# 02_Top_Level.net
KiCad netlist of a schematic drawn in Altium Designer
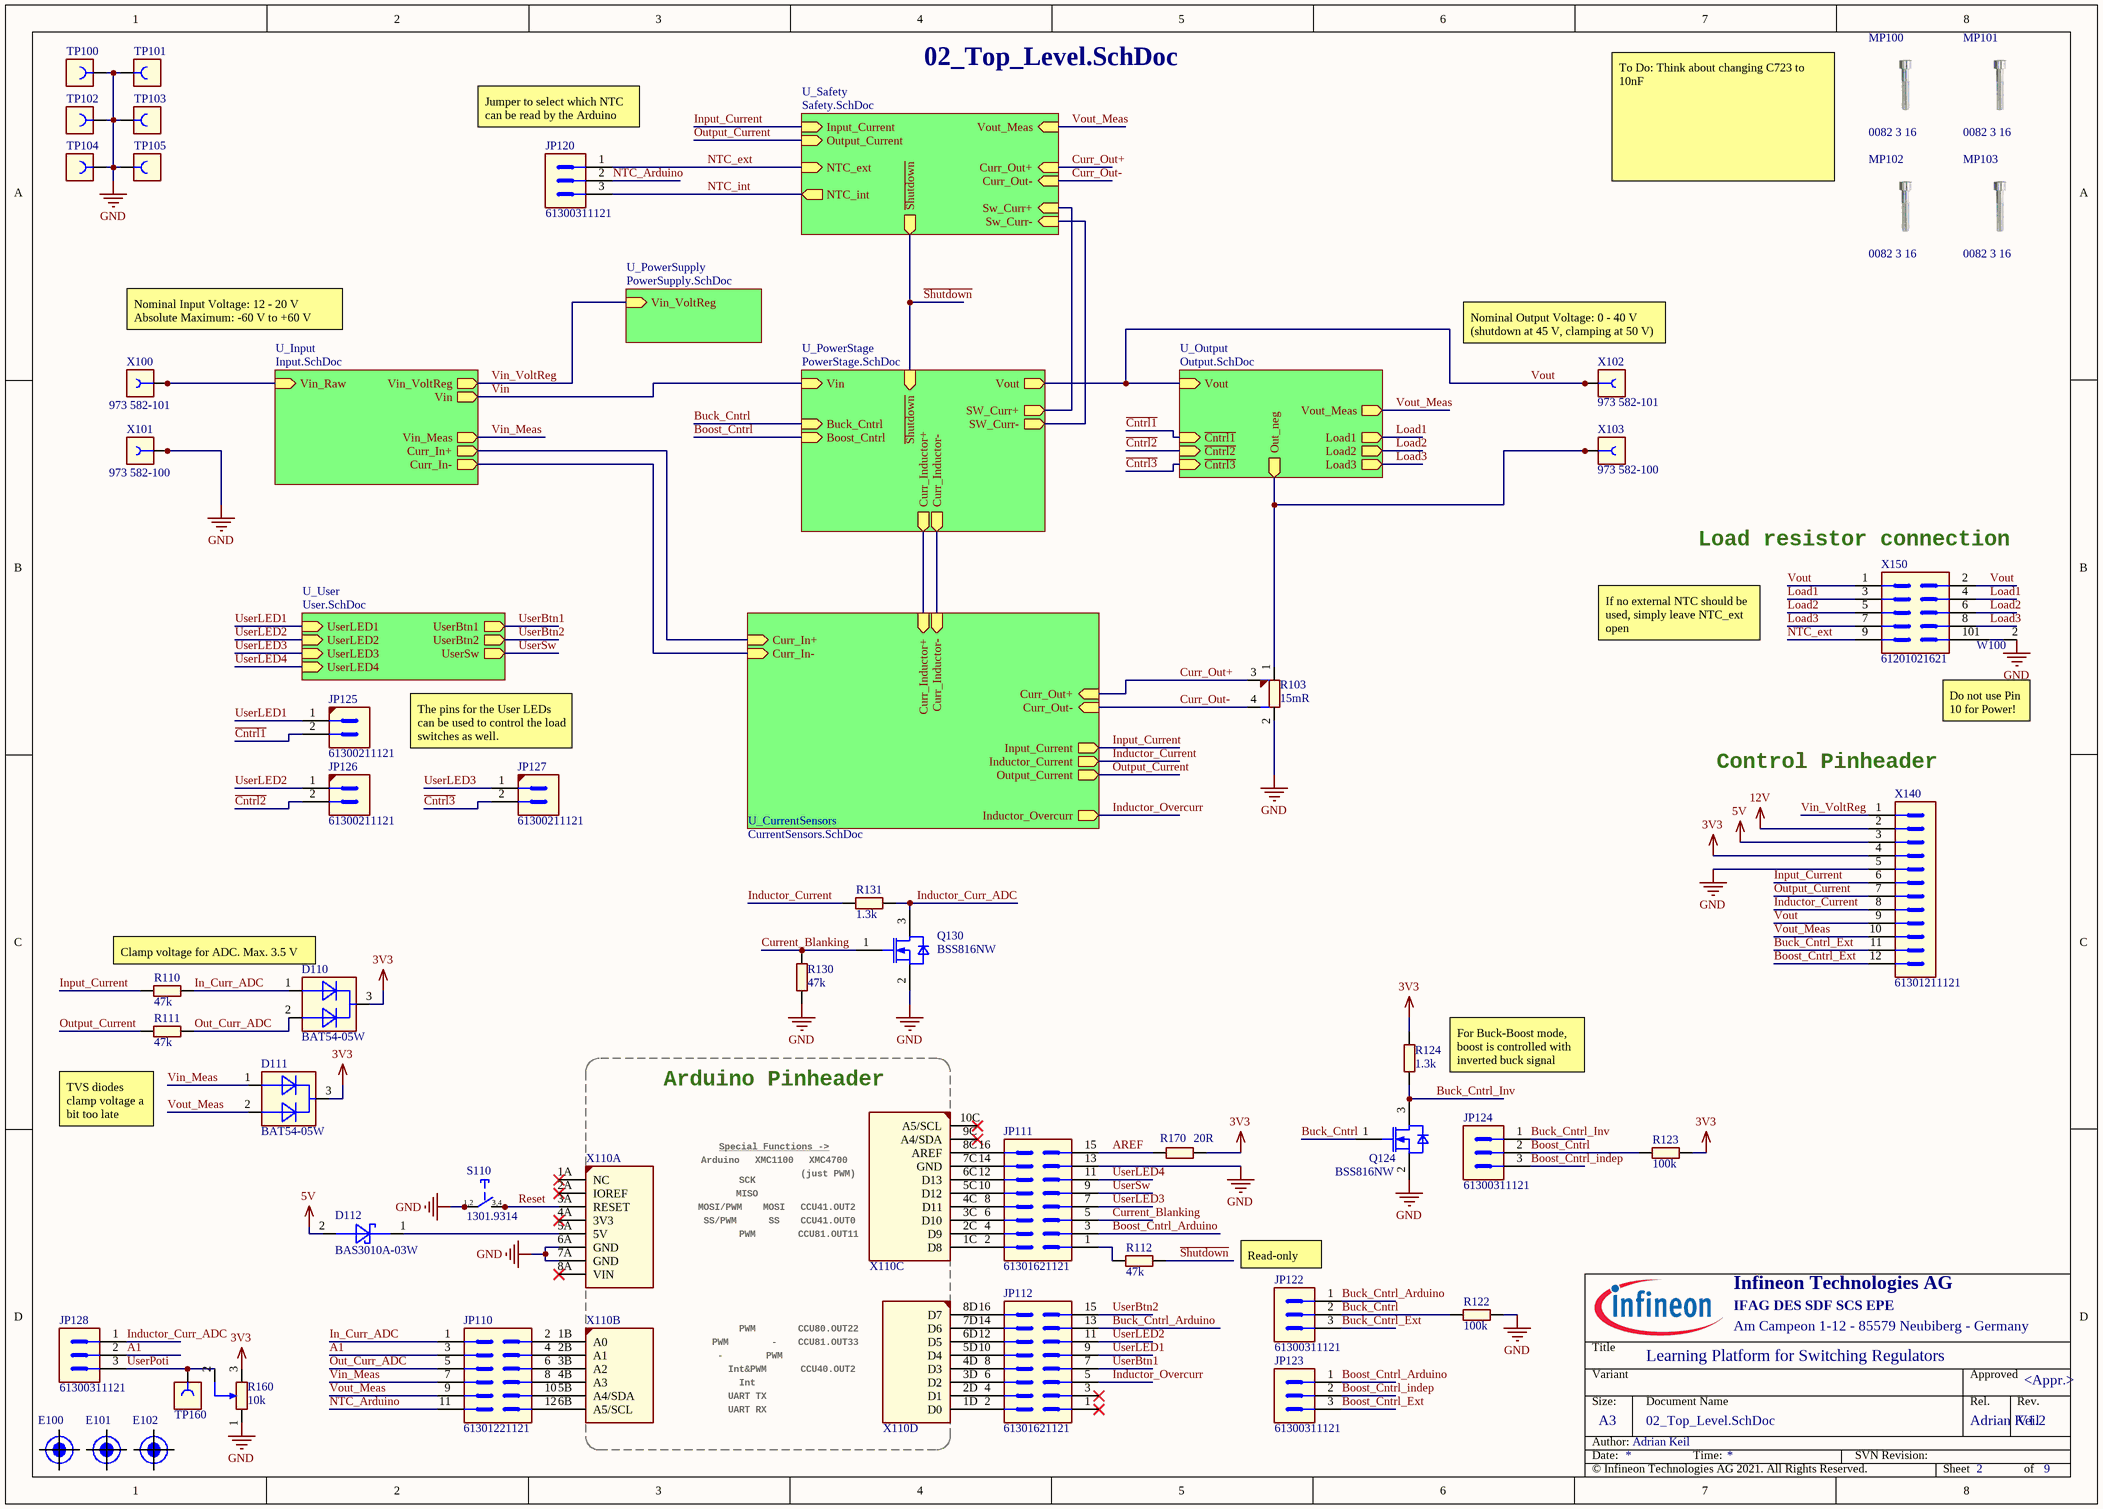
[diagram p0: 02_Top_Level.SchDoc]

(export (version "E")
  (design (tool "Eeschema 10.0.6"))
  (components
    (comp (ref "D110")
      (value "BAT54-05W")
      (footprint "SOT65P210X100-3N-1-V")
      (description "Silicon Schottky Diode, VR 30V")
      (fields (field (name "MANUFACTURER") "Infineon Technologies"))
      (libsource (lib "PCBLibraryData") (part "d_dual_a1a2c3_3p"))
    )
    (comp (ref "D111")
      (value "BAT54-05W")
      (footprint "SOT65P210X100-3N-1-V")
      (description "Silicon Schottky Diode, VR 30V")
      (fields (field (name "MANUFACTURER") "Infineon Technologies"))
      (libsource (lib "PCBLibraryData") (part "d_dual_a1a2c3_3p"))
    )
    (comp (ref "D112")
      (value "BAS3010A-03W")
      (footprint "SOD2513X110N")
      (description "Medium Power AF Schottky Diode")
      (fields
        (field (name "LEGACY PARTNUMBER") "IFX01400145")
        (field (name "MANUFACTURER") "Infineon Technologies")
      )
      (libsource (lib "PCBLibraryData") (part "d_schottky_a"))
    )
    (comp (ref "E100")
      (value "~")
      (footprint "fiducial")
      (description "Fiducial Mark")
      (fields
        (field (name "LEGACY PARTNUMBER") "MEC10000008")
        (field (name "MANUFACTURER") "Infineon Technologies")
      )
      (libsource (lib "PCBLibraryData") (part "fiducial"))
    )
    (comp (ref "E101")
      (value "~")
      (footprint "fiducial")
      (description "Fiducial Mark")
      (fields
        (field (name "LEGACY PARTNUMBER") "MEC10000008")
        (field (name "MANUFACTURER") "Infineon Technologies")
      )
      (libsource (lib "PCBLibraryData") (part "fiducial"))
    )
    (comp (ref "E102")
      (value "~")
      (footprint "fiducial")
      (description "Fiducial Mark")
      (fields
        (field (name "LEGACY PARTNUMBER") "MEC10000008")
        (field (name "MANUFACTURER") "Infineon Technologies")
      )
      (libsource (lib "PCBLibraryData") (part "fiducial"))
    )
    (comp (ref "JP110")
      (value "61301221121")
      (footprint "CON-M-THT-61301221121")
      (description "WR-PHD Dual Pin Header, 2.54mm Pitch, Double row, 12 Pins")
      (fields (field (name "MANUFACTURER") "Wurth Elektronik"))
      (libsource (lib "PCBLibraryData") (part "Header 6x2"))
    )
    (comp (ref "JP111")
      (value "61301621121")
      (footprint "CON-M-THT-61301621121")
      (description "Connector Header Through Hole 16 position 0.100 (2.54mm)")
      (fields (field (name "MANUFACTURER") "Wurth Elektronik"))
      (libsource (lib "PCBLibraryData") (part "Header 8X2"))
    )
    (comp (ref "JP112")
      (value "61301621121")
      (footprint "CON-M-THT-61301621121")
      (description "Connector Header Through Hole 16 position 0.100 (2.54mm)")
      (fields (field (name "MANUFACTURER") "Wurth Elektronik"))
      (libsource (lib "PCBLibraryData") (part "Header 8X2"))
    )
    (comp (ref "JP120")
      (value "61300311121")
      (footprint "CON-M-THT-61300311121")
      (description "WR-PHD Pin Header")
      (fields (field (name "MANUFACTURER") "Wurth Elektronik"))
      (libsource (lib "PCBLibraryData") (part "Header 3"))
    )
    (comp (ref "JP122")
      (value "61300311121")
      (footprint "CON-M-THT-61300311121")
      (description "WR-PHD Pin Header")
      (fields (field (name "MANUFACTURER") "Wurth Elektronik"))
      (libsource (lib "PCBLibraryData") (part "Header 3"))
    )
    (comp (ref "JP123")
      (value "61300311121")
      (footprint "CON-M-THT-61300311121")
      (description "WR-PHD Pin Header")
      (fields (field (name "MANUFACTURER") "Wurth Elektronik"))
      (libsource (lib "PCBLibraryData") (part "Header 3"))
    )
    (comp (ref "JP124")
      (value "61300311121")
      (footprint "CON-M-THT-61300311121")
      (description "WR-PHD Pin Header")
      (fields (field (name "MANUFACTURER") "Wurth Elektronik"))
      (libsource (lib "PCBLibraryData") (part "Header 3"))
    )
    (comp (ref "JP125")
      (value "61300211121")
      (footprint "CON-M-THT-61300211121")
      (description "Header, 2.54mm Pitch, 2 pin, Vertical, Single Row")
      (fields
        (field (name "LEGACY PARTNUMBER") "CON01500943")
        (field (name "MANUFACTURER") "Wurth Elektronik")
      )
      (libsource (lib "PCBLibraryData") (part "Header 2"))
    )
    (comp (ref "JP126")
      (value "61300211121")
      (footprint "CON-M-THT-61300211121")
      (description "Header, 2.54mm Pitch, 2 pin, Vertical, Single Row")
      (fields
        (field (name "LEGACY PARTNUMBER") "CON01500943")
        (field (name "MANUFACTURER") "Wurth Elektronik")
      )
      (libsource (lib "PCBLibraryData") (part "Header 2"))
    )
    (comp (ref "JP127")
      (value "61300211121")
      (footprint "CON-M-THT-61300211121")
      (description "Header, 2.54mm Pitch, 2 pin, Vertical, Single Row")
      (fields
        (field (name "LEGACY PARTNUMBER") "CON01500943")
        (field (name "MANUFACTURER") "Wurth Elektronik")
      )
      (libsource (lib "PCBLibraryData") (part "Header 2"))
    )
    (comp (ref "JP128")
      (value "61300311121")
      (footprint "CON-M-THT-61300311121")
      (description "WR-PHD Pin Header")
      (fields (field (name "MANUFACTURER") "Wurth Elektronik"))
      (libsource (lib "PCBLibraryData") (part "Header 3"))
    )
    (comp (ref "MP100")
      (value "0082 3 16")
      (footprint "SCREW_0082 3 16_NPTH")
      (description "Cheese Head Screw With Hexagon Socket, DIN 912 (ISO 4762), M3, 16mm length")
      (fields
        (field (name "LEGACY PARTNUMBER") "MEC10000167")
        (field (name "MANUFACTURER") "Wurth Elektronik")
      )
      (libsource (lib "PCBLibraryData") (part "Screw_0082 3 16"))
    )
    (comp (ref "MP101")
      (value "0082 3 16")
      (footprint "SCREW_0082 3 16_NPTH")
      (description "Cheese Head Screw With Hexagon Socket, DIN 912 (ISO 4762), M3, 16mm length")
      (fields
        (field (name "LEGACY PARTNUMBER") "MEC10000167")
        (field (name "MANUFACTURER") "Wurth Elektronik")
      )
      (libsource (lib "PCBLibraryData") (part "Screw_0082 3 16"))
    )
    (comp (ref "MP102")
      (value "0082 3 16")
      (footprint "SCREW_0082 3 16_NPTH")
      (description "Cheese Head Screw With Hexagon Socket, DIN 912 (ISO 4762), M3, 16mm length")
      (fields
        (field (name "LEGACY PARTNUMBER") "MEC10000167")
        (field (name "MANUFACTURER") "Wurth Elektronik")
      )
      (libsource (lib "PCBLibraryData") (part "Screw_0082 3 16"))
    )
    (comp (ref "MP103")
      (value "0082 3 16")
      (footprint "SCREW_0082 3 16_NPTH")
      (description "Cheese Head Screw With Hexagon Socket, DIN 912 (ISO 4762), M3, 16mm length")
      (fields
        (field (name "LEGACY PARTNUMBER") "MEC10000167")
        (field (name "MANUFACTURER") "Wurth Elektronik")
      )
      (libsource (lib "PCBLibraryData") (part "Screw_0082 3 16"))
    )
    (comp (ref "Q124")
      (value "BSS816NW")
      (footprint "SOT65P210X100-3N-1-V")
      (description "OptiMOS 2 Small-Signal-Transistor")
      (fields (field (name "MANUFACTURER") "Infineon Technologies"))
      (libsource (lib "PCBLibraryData") (part "igfet_n_ch_dep_dio_1g2s3d_3p"))
    )
    (comp (ref "Q130")
      (value "BSS816NW")
      (footprint "SOT65P210X100-3N-1-V")
      (description "OptiMOS 2 Small-Signal-Transistor")
      (fields (field (name "MANUFACTURER") "Infineon Technologies"))
      (libsource (lib "PCBLibraryData") (part "igfet_n_ch_dep_dio_1g2s3d_3p"))
    )
    (comp (ref "R103")
      (value "15mR")
      (footprint "RES-SMD-L4T12")
      (description "RES / STD / 15mR / 500mW / 1% / 75ppm/K / -55°C to 155°C / 1206 (3216) / SMD / -")
      (fields (field (name "MANUFACTURER") "Ohmite"))
      (libsource (lib "PCBLibraryData") (part "RES-SHT-STD-04P_00097BE5"))
    )
    (comp (ref "R110")
      (value "47k")
      (footprint "RESC1609X50N")
      (description "RES / STD / 47k / 100mW / 1% / 100ppm/K / -55°C to 155°C / 0603 / SMD / -")
      (fields (field (name "LEGACY PARTNUMBER") "RES01801333") (field (name "MANUFACTURER") "Vishay"))
      (libsource (lib "PCBLibraryData") (part "RES-SGL-STD-02P_00000006"))
    )
    (comp (ref "R111")
      (value "47k")
      (footprint "RESC1609X50N")
      (description "RES / STD / 47k / 100mW / 1% / 100ppm/K / -55°C to 155°C / 0603 / SMD / -")
      (fields (field (name "LEGACY PARTNUMBER") "RES01801333") (field (name "MANUFACTURER") "Vishay"))
      (libsource (lib "PCBLibraryData") (part "RES-SGL-STD-02P_00000006"))
    )
    (comp (ref "R112")
      (value "47k")
      (footprint "RESC1609X50N")
      (description "RES / STD / 47k / 100mW / 1% / 100ppm/K / -55°C to 155°C / 0603 / SMD / -")
      (fields (field (name "LEGACY PARTNUMBER") "RES01801333") (field (name "MANUFACTURER") "Vishay"))
      (libsource (lib "PCBLibraryData") (part "RES-SGL-STD-02P_00000006"))
    )
    (comp (ref "R122")
      (value "100k")
      (footprint "RESC1609X50N")
      (description "RES / STD / 100k / 100mW / 1% / 100ppm/K / -55°C to 155°C / 0603 / SMD / -")
      (fields (field (name "LEGACY PARTNUMBER") "RES01801371") (field (name "MANUFACTURER") "Vishay"))
      (libsource (lib "PCBLibraryData") (part "RES-SGL-STD-02P_00000006"))
    )
    (comp (ref "R123")
      (value "100k")
      (footprint "RESC1609X50N")
      (description "RES / STD / 100k / 100mW / 1% / 100ppm/K / -55°C to 155°C / 0603 / SMD / -")
      (fields (field (name "LEGACY PARTNUMBER") "RES01801371") (field (name "MANUFACTURER") "Vishay"))
      (libsource (lib "PCBLibraryData") (part "RES-SGL-STD-02P_00000006"))
    )
    (comp (ref "R124")
      (value "1.3k")
      (footprint "RESC1609X50N")
      (description "RES / STD / 1.3k / 100mW / 1% / 100ppm/K / -55°C to 155°C / 0603 / SMD / -")
      (fields (field (name "LEGACY PARTNUMBER") "RES01801155") (field (name "MANUFACTURER") "Vishay"))
      (libsource (lib "") (part "RES-SGL-STD-02P_00000006_1"))
    )
    (comp (ref "R130")
      (value "47k")
      (footprint "RESC1609X50N")
      (description "RES / STD / 47k / 100mW / 1% / 100ppm/K / -55°C to 155°C / 0603 / SMD / -")
      (fields (field (name "LEGACY PARTNUMBER") "RES01801333") (field (name "MANUFACTURER") "Vishay"))
      (libsource (lib "") (part "RES-SGL-STD-02P_00000006_1"))
    )
    (comp (ref "R131")
      (value "1.3k")
      (footprint "RESC1609X50N")
      (description "RES / STD / 1.3k / 100mW / 1% / 100ppm/K / -55°C to 155°C / 0603 / SMD / -")
      (fields (field (name "LEGACY PARTNUMBER") "RES01801155") (field (name "MANUFACTURER") "Vishay"))
      (libsource (lib "PCBLibraryData") (part "RES-SGL-STD-02P_00000006"))
    )
    (comp (ref "R160")
      (value "10k")
      (footprint "POT-SMD-3361P")
      (fields (field (name "MANUFACTURER") "Bourns"))
      (libsource (lib "PCBLibraryData") (part "RES-SGL-VAR-03P_00000026"))
    )
    (comp (ref "R170")
      (value "20R")
      (footprint "RESC1609X50N")
      (description "RES / STD / 20R / 100mW / 1% / 100ppm/K / -55°C to 155°C / 0603 / SMD / -")
      (fields (field (name "LEGACY PARTNUMBER") "RES01800947") (field (name "MANUFACTURER") "Vishay"))
      (libsource (lib "") (part "RES-SGL-STD-02P_00000006_2"))
    )
    (comp (ref "S110")
      (value "1301.9314")
      (footprint "SW-SMD-1301.9314")
      (description "Pushbutton Tactile Switch, Single Pole Single Throw, 4 Pins")
      (fields (field (name "LEGACY PARTNUMBER") "CON01500305") (field (name "MANUFACTURER") "Schurter"))
      (libsource (lib "PCBLibraryData") (part "sw_sr_no12_34_4p"))
    )
    (comp (ref "TP100")
      (value "5011")
      (footprint "CON-THT-TP-5011")
      (description "PC Test Point-Multipurpose THT, Black")
      (fields
        (field (name "LEGACY PARTNUMBER") "CON01500530")
        (field (name "MANUFACTURER") "Keystone Electronics Corp.")
      )
      (libsource (lib "PCBLibraryData") (part "connector_1_f"))
    )
    (comp (ref "TP101")
      (value "5011")
      (footprint "CON-THT-TP-5011")
      (description "PC Test Point-Multipurpose THT, Black")
      (fields
        (field (name "LEGACY PARTNUMBER") "CON01500530")
        (field (name "MANUFACTURER") "Keystone Electronics Corp.")
      )
      (libsource (lib "") (part "connector_1_f_1"))
    )
    (comp (ref "TP102")
      (value "5011")
      (footprint "CON-THT-TP-5011")
      (description "PC Test Point-Multipurpose THT, Black")
      (fields
        (field (name "LEGACY PARTNUMBER") "CON01500530")
        (field (name "MANUFACTURER") "Keystone Electronics Corp.")
      )
      (libsource (lib "PCBLibraryData") (part "connector_1_f"))
    )
    (comp (ref "TP103")
      (value "5011")
      (footprint "CON-THT-TP-5011")
      (description "PC Test Point-Multipurpose THT, Black")
      (fields
        (field (name "LEGACY PARTNUMBER") "CON01500530")
        (field (name "MANUFACTURER") "Keystone Electronics Corp.")
      )
      (libsource (lib "") (part "connector_1_f_1"))
    )
    (comp (ref "TP104")
      (value "5011")
      (footprint "CON-THT-TP-5011")
      (description "PC Test Point-Multipurpose THT, Black")
      (fields
        (field (name "LEGACY PARTNUMBER") "CON01500530")
        (field (name "MANUFACTURER") "Keystone Electronics Corp.")
      )
      (libsource (lib "PCBLibraryData") (part "connector_1_f"))
    )
    (comp (ref "TP105")
      (value "5011")
      (footprint "CON-THT-TP-5011")
      (description "PC Test Point-Multipurpose THT, Black")
      (fields
        (field (name "LEGACY PARTNUMBER") "CON01500530")
        (field (name "MANUFACTURER") "Keystone Electronics Corp.")
      )
      (libsource (lib "") (part "connector_1_f_1"))
    )
    (comp (ref "TP160")
      (value "S1751-46R")
      (footprint "CON-SMD-TT-S1751-46")
      (description "Test Terminal, Surface Mount (Tape and Reeled Components)")
      (fields (field (name "LEGACY PARTNUMBER") "CON01501015") (field (name "MANUFACTURER") "Harwin"))
      (libsource (lib "") (part "connector_1_f_2"))
    )
    (comp (ref "W100")
      (value "Net_Tie_2")
      (footprint "Net_Tie_Small_2P")
      (description "SMD Net Tie for two Nets")
      (fields
        (field (name "LEGACY PARTNUMBER") "CON01501379")
        (field (name "MANUFACTURER") "Infineon Technologies")
      )
      (libsource (lib "PCBLibraryData") (part "Net_Tie_2"))
    )
    (comp (ref "X100")
      (value "973 582-101")
      (footprint "CON-THT-973 582- 101")
      (description "Banana Socket, Red, 17.5mm Pitch")
      (fields
        (field (name "LEGACY PARTNUMBER") "CON01500041")
        (field (name "MANUFACTURER") "Hirschmann Test & Measurement")
      )
      (libsource (lib "PCBLibraryData") (part "soc_banana_2p"))
    )
    (comp (ref "X101")
      (value "973 582-100")
      (footprint "CON-THT-973 582- 100")
      (description "Banana Socket, black, 17.5mm Pitch")
      (fields
        (field (name "LEGACY PARTNUMBER") "CON01500045")
        (field (name "MANUFACTURER") "Hirschmann Test & Measurement")
      )
      (libsource (lib "PCBLibraryData") (part "soc_banana_2p"))
    )
    (comp (ref "X102")
      (value "973 582-101")
      (footprint "CON-THT-973 582- 101")
      (description "Banana Socket, Red, 17.5mm Pitch")
      (fields
        (field (name "LEGACY PARTNUMBER") "CON01500041")
        (field (name "MANUFACTURER") "Hirschmann Test & Measurement")
      )
      (libsource (lib "") (part "soc_banana_2p_1"))
    )
    (comp (ref "X103")
      (value "973 582-100")
      (footprint "CON-THT-973 582- 100")
      (description "Banana Socket, black, 17.5mm Pitch")
      (fields
        (field (name "LEGACY PARTNUMBER") "CON01500045")
        (field (name "MANUFACTURER") "Hirschmann Test & Measurement")
      )
      (libsource (lib "") (part "soc_banana_2p_1"))
    )
    (comp (ref "X110")
      (value "Arduino-Uno")
      (footprint "Arduino-Uno")
      (description "Arduino Uno is a microcontroller board based on the ATmega328P")
      (fields (field (name "MANUFACTURER") "Infineon Technologies"))
      (libsource (lib "") (part "Arduino-Uno_1"))
    )
    (comp (ref "X140")
      (value "61301211121")
      (footprint "CON-M-THT-61301211121")
      (description "WR-PHD Pin Header")
      (fields (field (name "MANUFACTURER") "Wurth Elektronik"))
      (libsource (lib "PCBLibraryData") (part "Header 12"))
    )
    (comp (ref "X150")
      (value "61201021621")
      (footprint "CON-M-THT-61201021621")
      (description "WR-BHD Male Box Header, 2.54mm pitch, 10 pin, Vertical, Double row")
      (fields (field (name "MANUFACTURER") "Wurth Elektronik"))
      (libsource (lib "PCBLibraryData") (part "Header 5X2"))
    )
  )
  (nets
    (net (code "1") (name "/A1") (class "Default")
      (node (ref "JP110") (pin "3") (pinfunction "3_3") (pintype "passive"))
      (node (ref "JP128") (pin "2") (pinfunction "2_2") (pintype "passive"))
    )
    (net (code "2") (name "/AREF") (class "Default")
      (node (ref "JP111") (pin "15") (pinfunction "15_15") (pintype "passive"))
      (node (ref "R170") (pin "1") (pinfunction "1_1") (pintype "passive"))
    )
    (net (code "3") (name "/Boost_Cntrl") (class "Default")
      (node (ref "JP124") (pin "2") (pinfunction "2_2") (pintype "passive"))
      (node (ref "R123") (pin "2") (pinfunction "2_2") (pintype "passive"))
    )
    (net (code "4") (name "/Boost_Cntrl_Arduino") (class "Default")
      (node (ref "JP111") (pin "3") (pinfunction "3_3") (pintype "passive"))
      (node (ref "JP123") (pin "1") (pinfunction "1_1") (pintype "passive"))
    )
    (net (code "5") (name "/Boost_Cntrl_Ext") (class "Default")
      (node (ref "JP123") (pin "3") (pinfunction "3_3") (pintype "passive"))
      (node (ref "X140") (pin "12") (pinfunction "12_12") (pintype "passive"))
    )
    (net (code "6") (name "/Boost_Cntrl_indep") (class "Default")
      (node (ref "JP123") (pin "2") (pinfunction "2_2") (pintype "passive"))
      (node (ref "JP124") (pin "3") (pinfunction "3_3") (pintype "passive"))
    )
    (net (code "7") (name "/Buck_Cntrl") (class "Default")
      (node (ref "JP122") (pin "2") (pinfunction "2_2") (pintype "passive"))
      (node (ref "Q124") (pin "1") (pinfunction "GATE_1") (pintype "passive"))
      (node (ref "R122") (pin "2") (pinfunction "2_2") (pintype "passive"))
    )
    (net (code "8") (name "/Buck_Cntrl_Arduino") (class "Default")
      (node (ref "JP112") (pin "13") (pinfunction "13_13") (pintype "passive"))
      (node (ref "JP122") (pin "1") (pinfunction "1_1") (pintype "passive"))
    )
    (net (code "9") (name "/Buck_Cntrl_Ext") (class "Default")
      (node (ref "JP122") (pin "3") (pinfunction "3_3") (pintype "passive"))
      (node (ref "X140") (pin "11") (pinfunction "11_11") (pintype "passive"))
    )
    (net (code "10") (name "/Buck_Cntrl_Inv") (class "Default")
      (node (ref "JP124") (pin "1") (pinfunction "1_1") (pintype "passive"))
      (node (ref "Q124") (pin "3") (pinfunction "DRAIN_3") (pintype "passive"))
      (node (ref "R124") (pin "1") (pinfunction "1_1") (pintype "passive"))
    )
    (net (code "11") (name "/Cntrl1") (class "Default")
      (node (ref "JP125") (pin "2") (pinfunction "2_2") (pintype "passive"))
    )
    (net (code "12") (name "/Cntrl2") (class "Default")
      (node (ref "JP126") (pin "2") (pinfunction "2_2") (pintype "passive"))
    )
    (net (code "13") (name "/Cntrl3") (class "Default")
      (node (ref "JP127") (pin "2") (pinfunction "2_2") (pintype "passive"))
    )
    (net (code "18") (name "/Curr_Out+") (class "Default")
      (node (ref "R103") (pin "3") (pinfunction "I1_3") (pintype "passive"))
    )
    (net (code "19") (name "/Curr_Out-") (class "Default")
      (node (ref "R103") (pin "4") (pinfunction "I2_4") (pintype "passive"))
    )
    (net (code "20") (name "/Current_Blanking") (class "Default")
      (node (ref "JP111") (pin "5") (pinfunction "5_5") (pintype "passive"))
      (node (ref "Q130") (pin "1") (pinfunction "GATE_1") (pintype "passive"))
      (node (ref "R130") (pin "2") (pinfunction "2_2") (pintype "passive"))
    )
    (net (code "21") (name "/In_Curr_ADC") (class "Default")
      (node (ref "D110") (pin "1") (pinfunction "ANODE_1_1") (pintype "passive"))
      (node (ref "JP110") (pin "1") (pinfunction "1_1") (pintype "passive"))
      (node (ref "R110") (pin "1") (pinfunction "1_1") (pintype "passive"))
    )
    (net (code "22") (name "/Inductor_Curr_ADC") (class "Default")
      (node (ref "JP128") (pin "1") (pinfunction "1_1") (pintype "passive"))
      (node (ref "Q130") (pin "3") (pinfunction "DRAIN_3") (pintype "passive"))
      (node (ref "R131") (pin "1") (pinfunction "1_1") (pintype "passive"))
    )
    (net (code "23") (name "/Inductor_Current") (class "Default")
      (node (ref "R131") (pin "2") (pinfunction "2_2") (pintype "passive"))
      (node (ref "X140") (pin "8") (pinfunction "8_8") (pintype "passive"))
    )
    (net (code "24") (name "/Inductor_Overcurr") (class "Default")
      (node (ref "JP112") (pin "5") (pinfunction "5_5") (pintype "passive"))
    )
    (net (code "25") (name "/Input_Current") (class "Default")
      (node (ref "R110") (pin "2") (pinfunction "2_2") (pintype "passive"))
      (node (ref "X140") (pin "6") (pinfunction "6_6") (pintype "passive"))
    )
    (net (code "26") (name "/Load1") (class "Default")
      (node (ref "X150") (pin "3") (pinfunction "3_3") (pintype "passive"))
      (node (ref "X150") (pin "4") (pinfunction "4_4") (pintype "passive"))
    )
    (net (code "27") (name "/Load2") (class "Default")
      (node (ref "X150") (pin "5") (pinfunction "5_5") (pintype "passive"))
      (node (ref "X150") (pin "6") (pinfunction "6_6") (pintype "passive"))
    )
    (net (code "28") (name "/Load3") (class "Default")
      (node (ref "X150") (pin "7") (pinfunction "7_7") (pintype "passive"))
      (node (ref "X150") (pin "8") (pinfunction "8_8") (pintype "passive"))
    )
    (net (code "29") (name "/NTC_Arduino") (class "Default")
      (node (ref "JP110") (pin "11") (pinfunction "11_11") (pintype "passive"))
      (node (ref "JP120") (pin "2") (pinfunction "2_2") (pintype "passive"))
    )
    (net (code "30") (name "/NTC_ext") (class "Default")
      (node (ref "JP120") (pin "1") (pinfunction "1_1") (pintype "passive"))
      (node (ref "X150") (pin "9") (pinfunction "9_9") (pintype "passive"))
    )
    (net (code "31") (name "/NTC_int") (class "Default")
      (node (ref "JP120") (pin "3") (pinfunction "3_3") (pintype "passive"))
    )
    (net (code "32") (name "/Out_Curr_ADC") (class "Default")
      (node (ref "D110") (pin "2") (pinfunction "ANODE_2_2") (pintype "passive"))
      (node (ref "JP110") (pin "5") (pinfunction "5_5") (pintype "passive"))
      (node (ref "R111") (pin "1") (pinfunction "1_1") (pintype "passive"))
    )
    (net (code "33") (name "/Out_neg") (class "Default")
      (node (ref "R103") (pin "1") (pinfunction "V1_1") (pintype "passive"))
      (node (ref "X103") (pin "1") (pinfunction "1_1") (pintype "passive"))
      (node (ref "X103") (pin "2") (pinfunction "2_2") (pintype "passive"))
    )
    (net (code "34") (name "/Output_Current") (class "Default")
      (node (ref "R111") (pin "2") (pinfunction "2_2") (pintype "passive"))
      (node (ref "X140") (pin "7") (pinfunction "7_7") (pintype "passive"))
    )
    (net (code "35") (name "/Reset") (class "Default")
      (node (ref "S110") (pin "3") (pinfunction "3_3") (pintype "passive"))
      (node (ref "S110") (pin "4") (pinfunction "4_4") (pintype "passive"))
      (node (ref "X110") (pin "3A") (pinfunction "RESET_3A") (pintype "passive"))
    )
    (net (code "38") (name "/Shutdown") (class "Default")
      (node (ref "R112") (pin "1") (pinfunction "1_1") (pintype "passive"))
    )
    (net (code "39") (name "/UserBtn1") (class "Default")
      (node (ref "JP112") (pin "7") (pinfunction "7_7") (pintype "passive"))
    )
    (net (code "40") (name "/UserBtn2") (class "Default")
      (node (ref "JP112") (pin "15") (pinfunction "15_15") (pintype "passive"))
    )
    (net (code "41") (name "/UserLED1") (class "Default")
      (node (ref "JP112") (pin "9") (pinfunction "9_9") (pintype "passive"))
      (node (ref "JP125") (pin "1") (pinfunction "1_1") (pintype "passive"))
    )
    (net (code "42") (name "/UserLED2") (class "Default")
      (node (ref "JP112") (pin "11") (pinfunction "11_11") (pintype "passive"))
      (node (ref "JP126") (pin "1") (pinfunction "1_1") (pintype "passive"))
    )
    (net (code "43") (name "/UserLED3") (class "Default")
      (node (ref "JP111") (pin "7") (pinfunction "7_7") (pintype "passive"))
      (node (ref "JP127") (pin "1") (pinfunction "1_1") (pintype "passive"))
    )
    (net (code "44") (name "/UserLED4") (class "Default")
      (node (ref "JP111") (pin "11") (pinfunction "11_11") (pintype "passive"))
    )
    (net (code "45") (name "/UserPoti") (class "Default")
      (node (ref "JP128") (pin "3") (pinfunction "3_3") (pintype "passive"))
      (node (ref "R160") (pin "2") (pinfunction "2_2") (pintype "passive"))
      (node (ref "TP160") (pin "1") (pinfunction "1_1") (pintype "passive"))
    )
    (net (code "46") (name "/UserSw") (class "Default")
      (node (ref "JP111") (pin "9") (pinfunction "9_9") (pintype "passive"))
    )
    (net (code "48") (name "/Vin_Meas") (class "Default")
      (node (ref "D111") (pin "1") (pinfunction "ANODE_1_1") (pintype "passive"))
      (node (ref "JP110") (pin "7") (pinfunction "7_7") (pintype "passive"))
    )
    (net (code "49") (name "/Vin_Raw") (class "Default")
      (node (ref "X100") (pin "1") (pinfunction "1_1") (pintype "passive"))
      (node (ref "X100") (pin "2") (pinfunction "2_2") (pintype "passive"))
    )
    (net (code "50") (name "/Vin_VoltReg") (class "Default")
      (node (ref "X140") (pin "1") (pinfunction "1_1") (pintype "passive"))
    )
    (net (code "51") (name "/Vout") (class "Default")
      (node (ref "X102") (pin "1") (pinfunction "1_1") (pintype "passive"))
      (node (ref "X102") (pin "2") (pinfunction "2_2") (pintype "passive"))
      (node (ref "X140") (pin "9") (pinfunction "9_9") (pintype "passive"))
      (node (ref "X150") (pin "1") (pinfunction "1_1") (pintype "passive"))
      (node (ref "X150") (pin "2") (pinfunction "2_2") (pintype "passive"))
    )
    (net (code "52") (name "/Vout_Meas") (class "Default")
      (node (ref "D111") (pin "2") (pinfunction "ANODE_2_2") (pintype "passive"))
      (node (ref "JP110") (pin "9") (pinfunction "9_9") (pintype "passive"))
      (node (ref "X140") (pin "10") (pinfunction "10_10") (pintype "passive"))
    )
    (net (code "53") (name "3V3") (class "Default")
      (node (ref "D110") (pin "3") (pinfunction "CATHODE_3") (pintype "passive"))
      (node (ref "D111") (pin "3") (pinfunction "CATHODE_3") (pintype "passive"))
      (node (ref "R123") (pin "1") (pinfunction "1_1") (pintype "passive"))
      (node (ref "R124") (pin "2") (pinfunction "2_2") (pintype "passive"))
      (node (ref "R160") (pin "3") (pinfunction "3_3") (pintype "passive"))
      (node (ref "R170") (pin "2") (pinfunction "2_2") (pintype "passive"))
      (node (ref "X140") (pin "4") (pinfunction "4_4") (pintype "passive"))
    )
    (net (code "54") (name "5V") (class "Default")
      (node (ref "D112") (pin "2") (pinfunction "Anode_2") (pintype "passive"))
      (node (ref "X140") (pin "3") (pinfunction "3_3") (pintype "passive"))
    )
    (net (code "55") (name "12V") (class "Default")
      (node (ref "X140") (pin "2") (pinfunction "2_2") (pintype "passive"))
    )
    (net (code "56") (name "GND") (class "Default")
      (node (ref "JP111") (pin "13") (pinfunction "13_13") (pintype "passive"))
      (node (ref "Q124") (pin "2") (pinfunction "SOURCE_2") (pintype "passive"))
      (node (ref "Q130") (pin "2") (pinfunction "SOURCE_2") (pintype "passive"))
      (node (ref "R103") (pin "2") (pinfunction "V2_2") (pintype "passive"))
      (node (ref "R122") (pin "1") (pinfunction "1_1") (pintype "passive"))
      (node (ref "R130") (pin "1") (pinfunction "1_1") (pintype "passive"))
      (node (ref "R160") (pin "1") (pinfunction "1_1") (pintype "passive"))
      (node (ref "S110") (pin "1") (pinfunction "1_1") (pintype "passive"))
      (node (ref "S110") (pin "2") (pinfunction "2_2") (pintype "passive"))
      (node (ref "TP100") (pin "1") (pinfunction "1_1") (pintype "passive"))
      (node (ref "TP101") (pin "1") (pinfunction "1_1") (pintype "passive"))
      (node (ref "TP102") (pin "1") (pinfunction "1_1") (pintype "passive"))
      (node (ref "TP103") (pin "1") (pinfunction "1_1") (pintype "passive"))
      (node (ref "TP104") (pin "1") (pinfunction "1_1") (pintype "passive"))
      (node (ref "TP105") (pin "1") (pinfunction "1_1") (pintype "passive"))
      (node (ref "W100") (pin "2") (pinfunction "2_2") (pintype "passive"))
      (node (ref "X101") (pin "1") (pinfunction "1_1") (pintype "passive"))
      (node (ref "X101") (pin "2") (pinfunction "2_2") (pintype "passive"))
      (node (ref "X110") (pin "6A") (pinfunction "GND_6A") (pintype "passive"))
      (node (ref "X110") (pin "7A") (pinfunction "GND_7A") (pintype "passive"))
      (node (ref "X140") (pin "5") (pinfunction "5_5") (pintype "passive"))
    )
    (net (code "57") (name "Net-(D112-Cathode)") (class "Default")
      (node (ref "D112") (pin "1") (pinfunction "Cathode_1") (pintype "passive"))
      (node (ref "X110") (pin "5A") (pinfunction "5V_5A") (pintype "passive"))
    )
    (net (code "58") (name "Net-(JP111-Pad1)") (class "Default")
      (node (ref "JP111") (pin "1") (pinfunction "1_1") (pintype "passive"))
      (node (ref "R112") (pin "2") (pinfunction "2_2") (pintype "passive"))
    )
    (net (code "59") (name "Net-(W100-Pad1)") (class "Default")
      (node (ref "W100") (pin "1") (pinfunction "1_1") (pintype "passive"))
      (node (ref "X150") (pin "10") (pinfunction "10_10") (pintype "passive"))
    )
    (net (code "60") (name "Net-(X110B-A0)") (class "Default")
      (node (ref "JP110") (pin "2") (pinfunction "2_2") (pintype "passive"))
      (node (ref "X110") (pin "1B") (pinfunction "A0_1B") (pintype "passive"))
    )
    (net (code "61") (name "Net-(X110B-A1)") (class "Default")
      (node (ref "JP110") (pin "4") (pinfunction "4_4") (pintype "passive"))
      (node (ref "X110") (pin "2B") (pinfunction "A1_2B") (pintype "passive"))
    )
    (net (code "62") (name "Net-(X110B-A2)") (class "Default")
      (node (ref "JP110") (pin "6") (pinfunction "6_6") (pintype "passive"))
      (node (ref "X110") (pin "3B") (pinfunction "A2_3B") (pintype "passive"))
    )
    (net (code "63") (name "Net-(X110B-A3)") (class "Default")
      (node (ref "JP110") (pin "8") (pinfunction "8_8") (pintype "passive"))
      (node (ref "X110") (pin "4B") (pinfunction "A3_4B") (pintype "passive"))
    )
    (net (code "64") (name "Net-(X110B-A4{slash}SDA)") (class "Default")
      (node (ref "JP110") (pin "10") (pinfunction "10_10") (pintype "passive"))
      (node (ref "X110") (pin "5B") (pinfunction "A4/SDA_5B") (pintype "passive"))
    )
    (net (code "65") (name "Net-(X110B-A5{slash}SCL)") (class "Default")
      (node (ref "JP110") (pin "12") (pinfunction "12_12") (pintype "passive"))
      (node (ref "X110") (pin "6B") (pinfunction "A5/SCL_6B") (pintype "passive"))
    )
    (net (code "66") (name "Net-(X110C-AREF)") (class "Default")
      (node (ref "JP111") (pin "16") (pinfunction "16_16") (pintype "passive"))
      (node (ref "X110") (pin "8C") (pinfunction "AREF_8C") (pintype "passive"))
    )
    (net (code "67") (name "Net-(X110C-D8)") (class "Default")
      (node (ref "JP111") (pin "2") (pinfunction "2_2") (pintype "passive"))
      (node (ref "X110") (pin "1C") (pinfunction "D8_1C") (pintype "passive"))
    )
    (net (code "68") (name "Net-(X110C-D9)") (class "Default")
      (node (ref "JP111") (pin "4") (pinfunction "4_4") (pintype "passive"))
      (node (ref "X110") (pin "2C") (pinfunction "D9_2C") (pintype "passive"))
    )
    (net (code "69") (name "Net-(X110C-D10)") (class "Default")
      (node (ref "JP111") (pin "6") (pinfunction "6_6") (pintype "passive"))
      (node (ref "X110") (pin "3C") (pinfunction "D10_3C") (pintype "passive"))
    )
    (net (code "70") (name "Net-(X110C-D11)") (class "Default")
      (node (ref "JP111") (pin "8") (pinfunction "8_8") (pintype "passive"))
      (node (ref "X110") (pin "4C") (pinfunction "D11_4C") (pintype "passive"))
    )
    (net (code "71") (name "Net-(X110C-D12)") (class "Default")
      (node (ref "JP111") (pin "10") (pinfunction "10_10") (pintype "passive"))
      (node (ref "X110") (pin "5C") (pinfunction "D12_5C") (pintype "passive"))
    )
    (net (code "72") (name "Net-(X110C-D13)") (class "Default")
      (node (ref "JP111") (pin "12") (pinfunction "12_12") (pintype "passive"))
      (node (ref "X110") (pin "6C") (pinfunction "D13_6C") (pintype "passive"))
    )
    (net (code "73") (name "Net-(X110C-GND)") (class "Default")
      (node (ref "JP111") (pin "14") (pinfunction "14_14") (pintype "passive"))
      (node (ref "X110") (pin "7C") (pinfunction "GND_7C") (pintype "passive"))
    )
    (net (code "74") (name "Net-(X110D-D0)") (class "Default")
      (node (ref "JP112") (pin "2") (pinfunction "2_2") (pintype "passive"))
      (node (ref "X110") (pin "1D") (pinfunction "D0_1D") (pintype "passive"))
    )
    (net (code "75") (name "Net-(X110D-D1)") (class "Default")
      (node (ref "JP112") (pin "4") (pinfunction "4_4") (pintype "passive"))
      (node (ref "X110") (pin "2D") (pinfunction "D1_2D") (pintype "passive"))
    )
    (net (code "76") (name "Net-(X110D-D2)") (class "Default")
      (node (ref "JP112") (pin "6") (pinfunction "6_6") (pintype "passive"))
      (node (ref "X110") (pin "3D") (pinfunction "D2_3D") (pintype "passive"))
    )
    (net (code "77") (name "Net-(X110D-D3)") (class "Default")
      (node (ref "JP112") (pin "8") (pinfunction "8_8") (pintype "passive"))
      (node (ref "X110") (pin "4D") (pinfunction "D3_4D") (pintype "passive"))
    )
    (net (code "78") (name "Net-(X110D-D4)") (class "Default")
      (node (ref "JP112") (pin "10") (pinfunction "10_10") (pintype "passive"))
      (node (ref "X110") (pin "5D") (pinfunction "D4_5D") (pintype "passive"))
    )
    (net (code "79") (name "Net-(X110D-D5)") (class "Default")
      (node (ref "JP112") (pin "12") (pinfunction "12_12") (pintype "passive"))
      (node (ref "X110") (pin "6D") (pinfunction "D5_6D") (pintype "passive"))
    )
    (net (code "80") (name "Net-(X110D-D6)") (class "Default")
      (node (ref "JP112") (pin "14") (pinfunction "14_14") (pintype "passive"))
      (node (ref "X110") (pin "7D") (pinfunction "D6_7D") (pintype "passive"))
    )
    (net (code "81") (name "Net-(X110D-D7)") (class "Default")
      (node (ref "JP112") (pin "16") (pinfunction "16_16") (pintype "passive"))
      (node (ref "X110") (pin "8D") (pinfunction "D7_8D") (pintype "passive"))
    )
    (net (code "82") (name "unconnected-(E100-Pad1)") (class "Default")
      (node (ref "E100") (pin "1") (pinfunction "1_1") (pintype "passive"))
    )
    (net (code "83") (name "unconnected-(E101-Pad1)") (class "Default")
      (node (ref "E101") (pin "1") (pinfunction "1_1") (pintype "passive"))
    )
    (net (code "84") (name "unconnected-(E102-Pad1)") (class "Default")
      (node (ref "E102") (pin "1") (pinfunction "1_1") (pintype "passive"))
    )
    (net (code "85") (name "unconnected-(JP112-Pad1)") (class "Default")
      (node (ref "JP112") (pin "1") (pinfunction "1_1") (pintype "passive+no_connect"))
    )
    (net (code "86") (name "unconnected-(JP112-Pad3)") (class "Default")
      (node (ref "JP112") (pin "3") (pinfunction "3_3") (pintype "passive+no_connect"))
    )
    (net (code "87") (name "unconnected-(X110A-3V3-Pad4A)") (class "Default")
      (node (ref "X110") (pin "4A") (pinfunction "3V3_4A") (pintype "passive+no_connect"))
    )
    (net (code "88") (name "unconnected-(X110A-IOREF-Pad2A)") (class "Default")
      (node (ref "X110") (pin "2A") (pinfunction "IOREF_2A") (pintype "passive+no_connect"))
    )
    (net (code "89") (name "unconnected-(X110A-NC-Pad1A)") (class "Default")
      (node (ref "X110") (pin "1A") (pinfunction "NC_1A") (pintype "passive+no_connect"))
    )
    (net (code "90") (name "unconnected-(X110A-VIN-Pad8A)") (class "Default")
      (node (ref "X110") (pin "8A") (pinfunction "VIN_8A") (pintype "passive+no_connect"))
    )
    (net (code "91") (name "unconnected-(X110C-A4{slash}SDA-Pad9C)") (class "Default")
      (node (ref "X110") (pin "9C") (pinfunction "A4/SDA_9C") (pintype "passive+no_connect"))
    )
    (net (code "92") (name "unconnected-(X110C-A5{slash}SCL-Pad10C)") (class "Default")
      (node (ref "X110") (pin "10C") (pinfunction "A5/SCL_10C") (pintype "passive+no_connect"))
    )
  )
)
